# max485.net
KiCad netlist of a schematic drawn in EAGLE
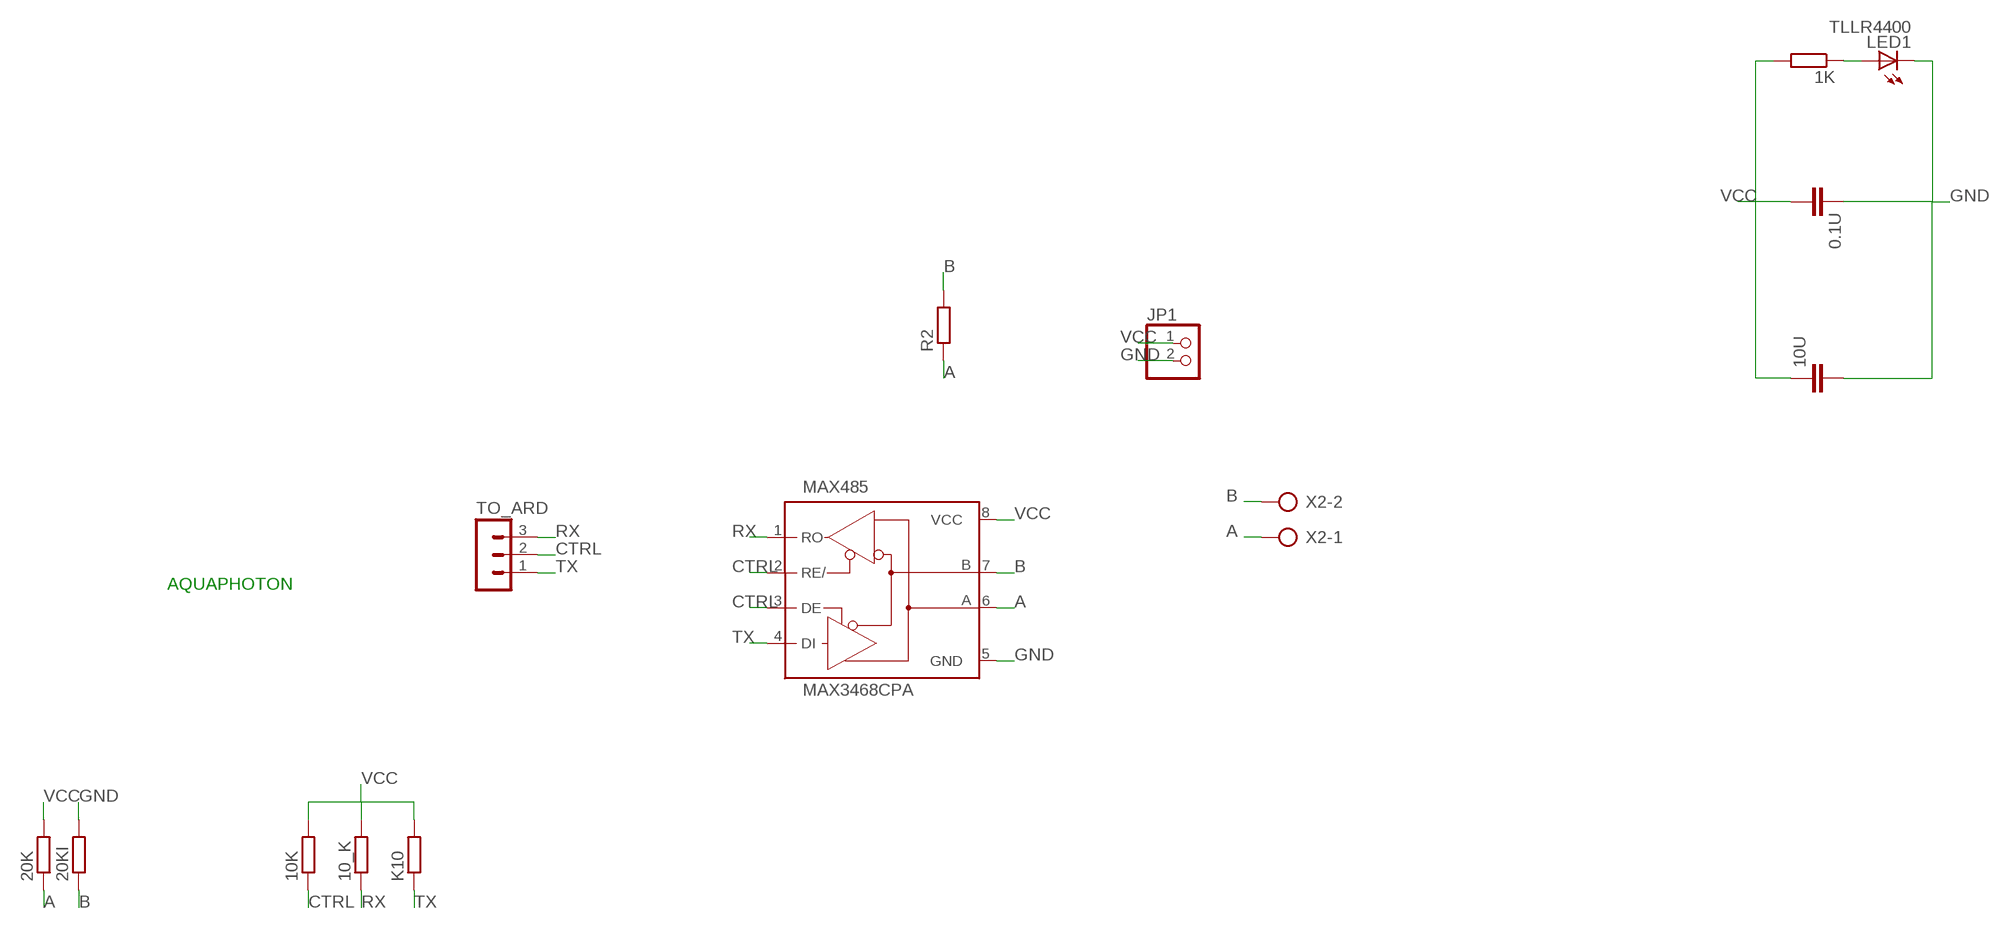
[diagram p0: schematic, sheet 1]

(export (version "E")
  (design (tool "Eeschema 10.0.6"))
  (components
    (comp (ref "0.1U")
      (value "C5/2.5")
      (footprint "eagle-import:C5B2.5")
      (libsource (lib "eagle-import") (part "C5/2.5"))
    )
    (comp (ref "1K")
      (value "R-EU_0207/10")
      (footprint "eagle-import:0207_10")
      (libsource (lib "eagle-import") (part "R-EU_0207/10"))
    )
    (comp (ref "10K")
      (value "R-EU_0207/10")
      (footprint "eagle-import:0207_10")
      (libsource (lib "eagle-import") (part "R-EU_0207/10"))
    )
    (comp (ref "10U")
      (value "C5/2.5")
      (footprint "eagle-import:C5B2.5")
      (libsource (lib "eagle-import") (part "C5/2.5"))
    )
    (comp (ref "10_K")
      (value "R-EU_0207/10")
      (footprint "eagle-import:0207_10")
      (libsource (lib "eagle-import") (part "R-EU_0207/10"))
    )
    (comp (ref "20K")
      (value "R-EU_0207/10")
      (footprint "eagle-import:0207_10")
      (libsource (lib "eagle-import") (part "R-EU_0207/10"))
    )
    (comp (ref "20KI")
      (value "R-EU_0207/10")
      (footprint "eagle-import:0207_10")
      (libsource (lib "eagle-import") (part "R-EU_0207/10"))
    )
    (comp (ref "JP1")
      (value "PINHD-1X2")
      (footprint "eagle-import:1X02")
      (libsource (lib "eagle-import") (part "PINHD-1X2"))
    )
    (comp (ref "K10")
      (value "R-EU_0207/10")
      (footprint "eagle-import:0207_10")
      (libsource (lib "eagle-import") (part "R-EU_0207/10"))
    )
    (comp (ref "LED1")
      (value "TLLR4400")
      (footprint "eagle-import:LED3MM")
      (fields (field (name "MF") "VISHAY SEMICONDUCTOR"))
      (libsource (lib "eagle-import") (part "TLLR4400"))
    )
    (comp (ref "MAX485")
      (value "MAX3468CPA")
      (footprint "eagle-import:DIL08")
      (libsource (lib "eagle-import") (part "MAX34PA68C"))
    )
    (comp (ref "R2")
      (value "R-EU_0207/10")
      (footprint "eagle-import:0207_10")
      (libsource (lib "eagle-import") (part "R-EU_0207/10"))
    )
    (comp (ref "TO_ARD")
      (value "MA03-1")
      (footprint "eagle-import:MA03-1")
      (libsource (lib "eagle-import") (part "MA03-1"))
    )
    (comp (ref "X2")
      (value "AK500/2-H")
      (footprint "eagle-import:AK500_2-H")
      (libsource (lib "eagle-import") (part "AK500/2-H"))
    )
  )
  (nets
    (net (code "1") (name "/A") (class "Default")
      (node (ref "20K") (pin "1") (pinfunction "1_1") (pintype "passive"))
      (node (ref "MAX485") (pin "6") (pinfunction "A_6") (pintype "passive"))
      (node (ref "R2") (pin "1") (pinfunction "1_1") (pintype "passive"))
      (node (ref "X2") (pin "1") (pinfunction "KL_1") (pintype "passive"))
    )
    (net (code "2") (name "/B") (class "Default")
      (node (ref "20KI") (pin "1") (pinfunction "1_1") (pintype "passive"))
      (node (ref "MAX485") (pin "7") (pinfunction "B_7") (pintype "passive"))
      (node (ref "R2") (pin "2") (pinfunction "2_2") (pintype "passive"))
      (node (ref "X2") (pin "2") (pinfunction "KL_2") (pintype "passive"))
    )
    (net (code "3") (name "/CTRL") (class "Default")
      (node (ref "10K") (pin "1") (pinfunction "1_1") (pintype "passive"))
      (node (ref "MAX485") (pin "2") (pinfunction "RE/_2") (pintype "input"))
      (node (ref "MAX485") (pin "3") (pinfunction "DE_3") (pintype "input"))
      (node (ref "TO_ARD") (pin "2") (pinfunction "2_2") (pintype "passive"))
    )
    (net (code "4") (name "/GND") (class "Default")
      (node (ref "0.1U") (pin "1") (pinfunction "1_1") (pintype "passive"))
      (node (ref "10U") (pin "2") (pinfunction "2_2") (pintype "passive"))
      (node (ref "20KI") (pin "2") (pinfunction "2_2") (pintype "passive"))
      (node (ref "JP1") (pin "2") (pinfunction "2_2") (pintype "passive"))
      (node (ref "LED1") (pin "K") (pinfunction "C_K") (pintype "passive"))
      (node (ref "MAX485") (pin "5") (pinfunction "GND_5") (pintype "power_in"))
    )
    (net (code "5") (name "/RX") (class "Default")
      (node (ref "10_K") (pin "1") (pinfunction "1_1") (pintype "passive"))
      (node (ref "MAX485") (pin "1") (pinfunction "RO_1") (pintype "output"))
      (node (ref "TO_ARD") (pin "3") (pinfunction "3_3") (pintype "passive"))
    )
    (net (code "6") (name "/TX") (class "Default")
      (node (ref "K10") (pin "1") (pinfunction "1_1") (pintype "passive"))
      (node (ref "MAX485") (pin "4") (pinfunction "DI_4") (pintype "input"))
      (node (ref "TO_ARD") (pin "1") (pinfunction "1_1") (pintype "passive"))
    )
    (net (code "7") (name "/VCC") (class "Default")
      (node (ref "0.1U") (pin "2") (pinfunction "2_2") (pintype "passive"))
      (node (ref "10K") (pin "2") (pinfunction "2_2") (pintype "passive"))
      (node (ref "10U") (pin "1") (pinfunction "1_1") (pintype "passive"))
      (node (ref "10_K") (pin "2") (pinfunction "2_2") (pintype "passive"))
      (node (ref "1K") (pin "2") (pinfunction "2_2") (pintype "passive"))
      (node (ref "20K") (pin "2") (pinfunction "2_2") (pintype "passive"))
      (node (ref "JP1") (pin "1") (pinfunction "1_1") (pintype "passive"))
      (node (ref "K10") (pin "2") (pinfunction "2_2") (pintype "passive"))
      (node (ref "MAX485") (pin "8") (pinfunction "VCC_8") (pintype "power_in"))
    )
    (net (code "8") (name "Net-(1K-Pad1)") (class "Default")
      (node (ref "1K") (pin "1") (pinfunction "1_1") (pintype "passive"))
      (node (ref "LED1") (pin "A") (pinfunction "A_A") (pintype "passive"))
    )
  )
)
